# RCMx1_Rev_02.net
KiCad netlist of a schematic drawn in EAGLE
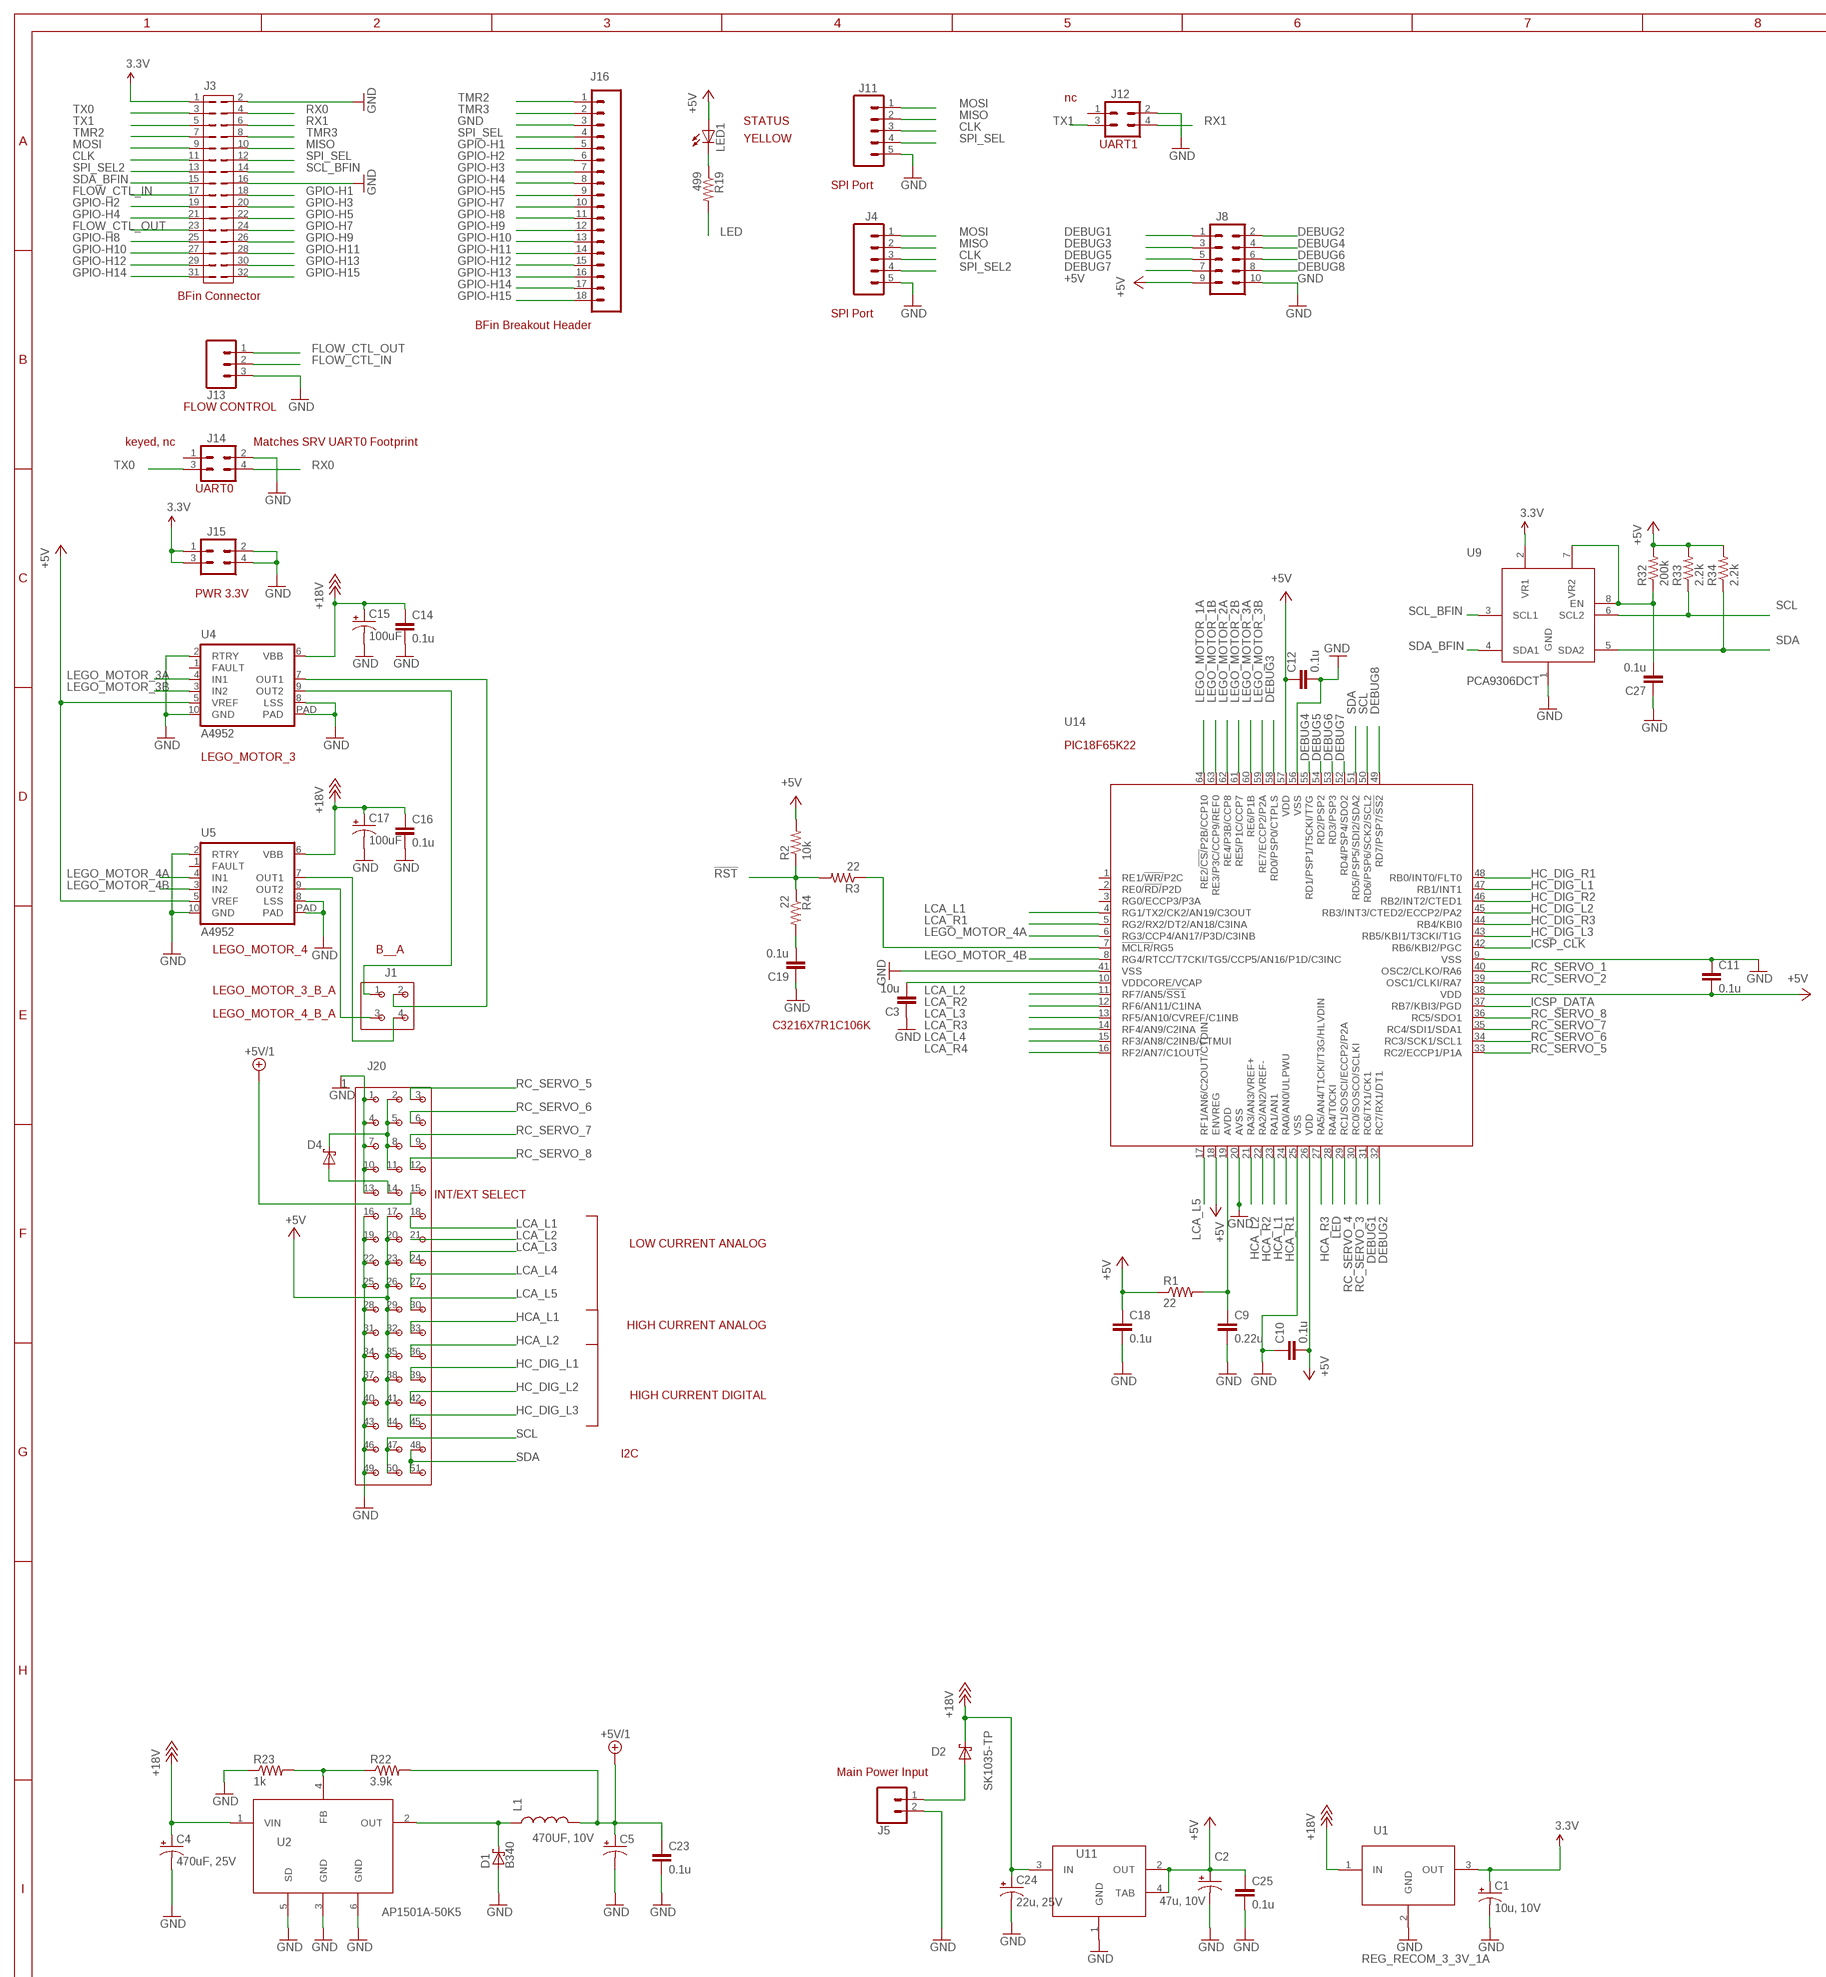
[diagram p0: schematic, sheet 1, part 1 of 2]
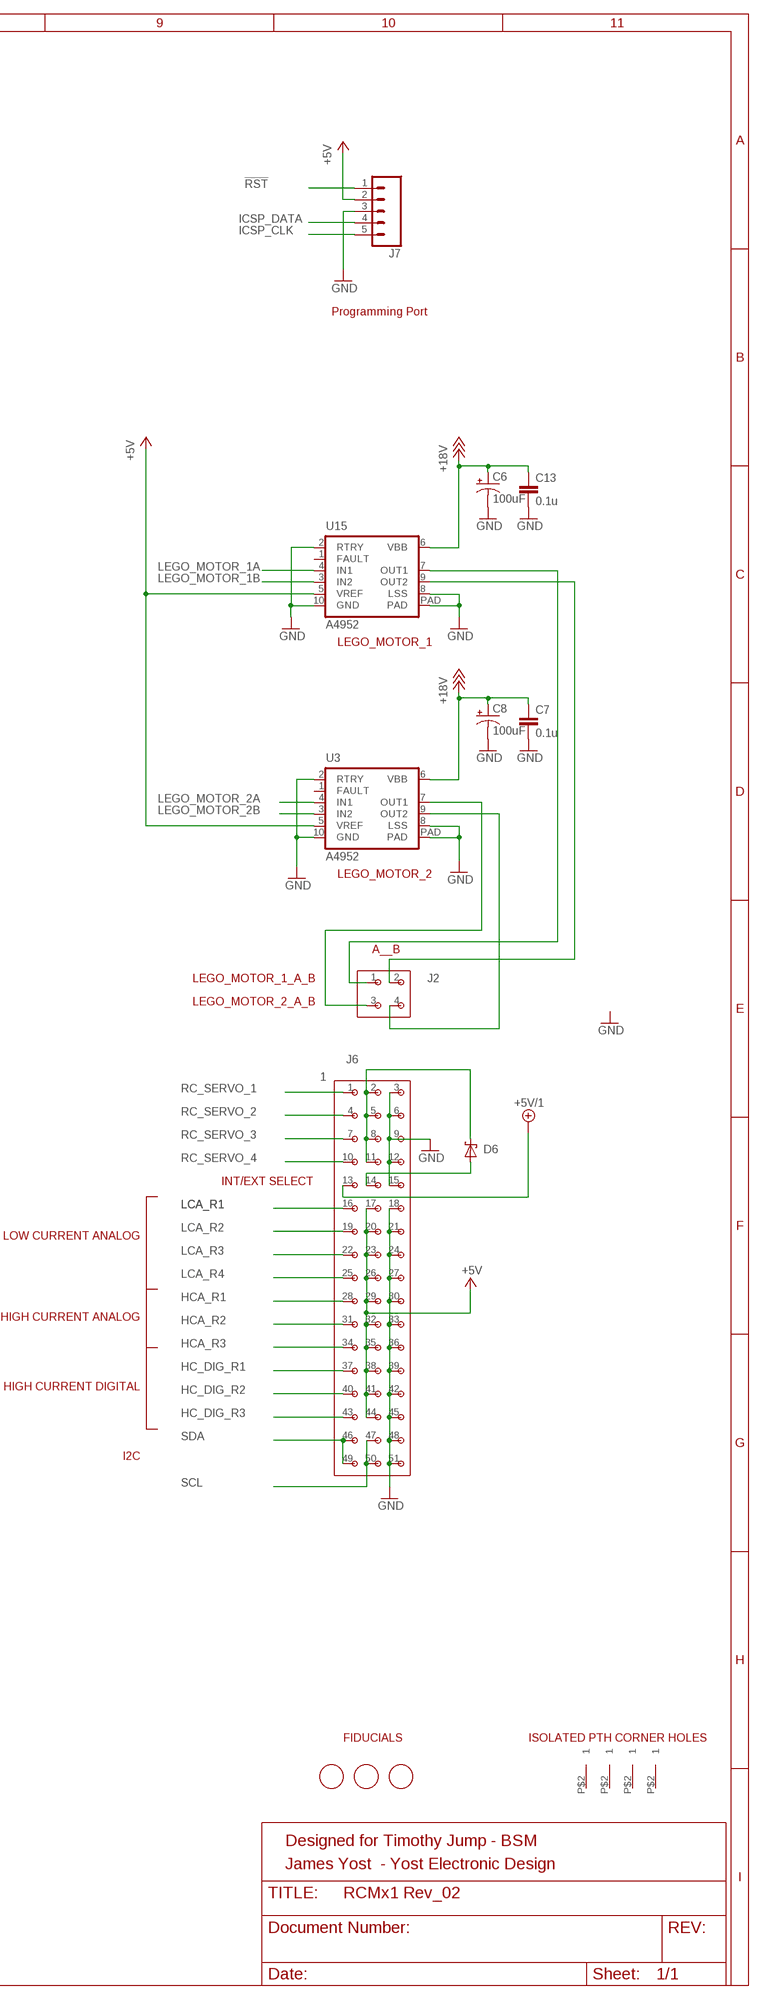
[diagram p1: schematic, sheet 1, part 2 of 2]

(export (version "E")
  (design (tool "Eeschema 10.0.6"))
  (components
    (comp (ref "C1")
      (value "10u, 10V")
      (footprint "eagle-import:EIA3216")
      (libsource (lib "eagle-import") (part "CAP_POL1206"))
    )
    (comp (ref "C2")
      (value "47u, 10V")
      (footprint "eagle-import:CAP1210_POL")
      (libsource (lib "eagle-import") (part "CAP_1210_POL"))
    )
    (comp (ref "C3")
      (value "10u")
      (footprint "eagle-import:1206")
      (libsource (lib "eagle-import") (part "CAP1206"))
    )
    (comp (ref "C4")
      (value "470uF, 25V")
      (footprint "eagle-import:PANASONIC_G")
      (libsource (lib "eagle-import") (part "CAP_POLG"))
    )
    (comp (ref "C5")
      (value "470UF, 10V")
      (footprint "eagle-import:PANASONIC_F")
      (libsource (lib "eagle-import") (part "CAP_ELT_PANASONIC_470UF"))
    )
    (comp (ref "C6")
      (value "100uF")
      (footprint "eagle-import:PANASONIC_D")
      (libsource (lib "eagle-import") (part "CAP_POLD"))
    )
    (comp (ref "C7")
      (value "0.1u")
      (footprint "eagle-import:0805")
      (libsource (lib "eagle-import") (part "CAP0805"))
    )
    (comp (ref "C8")
      (value "100uF")
      (footprint "eagle-import:PANASONIC_D")
      (libsource (lib "eagle-import") (part "CAP_POLD"))
    )
    (comp (ref "C9")
      (value "0.22u")
      (footprint "eagle-import:0805")
      (libsource (lib "eagle-import") (part "CAP0805"))
    )
    (comp (ref "C10")
      (value "0.1u")
      (footprint "eagle-import:0805")
      (libsource (lib "eagle-import") (part "CAP0805"))
    )
    (comp (ref "C11")
      (value "0.1u")
      (footprint "eagle-import:0805")
      (libsource (lib "eagle-import") (part "CAP0805"))
    )
    (comp (ref "C12")
      (value "0.1u")
      (footprint "eagle-import:0805")
      (libsource (lib "eagle-import") (part "CAP0805"))
    )
    (comp (ref "C13")
      (value "0.1u")
      (footprint "eagle-import:0805")
      (libsource (lib "eagle-import") (part "CAP0805"))
    )
    (comp (ref "C14")
      (value "0.1u")
      (footprint "eagle-import:0805")
      (libsource (lib "eagle-import") (part "CAP0805"))
    )
    (comp (ref "C15")
      (value "100uF")
      (footprint "eagle-import:PANASONIC_D")
      (libsource (lib "eagle-import") (part "CAP_POLD"))
    )
    (comp (ref "C16")
      (value "0.1u")
      (footprint "eagle-import:0805")
      (libsource (lib "eagle-import") (part "CAP0805"))
    )
    (comp (ref "C17")
      (value "100uF")
      (footprint "eagle-import:PANASONIC_D")
      (libsource (lib "eagle-import") (part "CAP_POLD"))
    )
    (comp (ref "C18")
      (value "0.1u")
      (footprint "eagle-import:0805")
      (libsource (lib "eagle-import") (part "CAP0805"))
    )
    (comp (ref "C19")
      (value "0.1u")
      (footprint "eagle-import:0805")
      (libsource (lib "eagle-import") (part "CAP0805"))
    )
    (comp (ref "C23")
      (value "0.1u")
      (footprint "eagle-import:0805")
      (libsource (lib "eagle-import") (part "CAP0805"))
    )
    (comp (ref "C24")
      (value "22u, 25V")
      (footprint "eagle-import:CAP1210_POL")
      (libsource (lib "eagle-import") (part "CAP_1210_POL"))
    )
    (comp (ref "C25")
      (value "0.1u")
      (footprint "eagle-import:0805")
      (libsource (lib "eagle-import") (part "CAP0805"))
    )
    (comp (ref "C27")
      (value "0.1u")
      (footprint "eagle-import:0805")
      (libsource (lib "eagle-import") (part "CAP0805"))
    )
    (comp (ref "D1")
      (value "B340")
      (footprint "eagle-import:SMA_DO214AC")
      (libsource (lib "eagle-import") (part "B340"))
    )
    (comp (ref "D2")
      (value "SK1035-TP")
      (footprint "eagle-import:DO214AB")
      (libsource (lib "eagle-import") (part "SK1035-TP"))
    )
    (comp (ref "D4")
      (value "SK1035-TP")
      (footprint "eagle-import:DO214AB")
      (libsource (lib "eagle-import") (part "SK1035-TP"))
    )
    (comp (ref "D6")
      (value "SK1035-TP")
      (footprint "eagle-import:DO214AB")
      (libsource (lib "eagle-import") (part "SK1035-TP"))
    )
    (comp (ref "FID1")
      (value "FIDUCIAL")
      (footprint "eagle-import:FIDUCIAL_1MM")
      (libsource (lib "eagle-import") (part "FIDUCIAL"))
    )
    (comp (ref "FID2")
      (value "FIDUCIAL")
      (footprint "eagle-import:FIDUCIAL_1MM")
      (libsource (lib "eagle-import") (part "FIDUCIAL"))
    )
    (comp (ref "FID3")
      (value "FIDUCIAL")
      (footprint "eagle-import:FIDUCIAL_1MM")
      (libsource (lib "eagle-import") (part "FIDUCIAL"))
    )
    (comp (ref "J1")
      (value "CON_2X2_0_100")
      (footprint "eagle-import:CON_2X2_0_100")
      (libsource (lib "eagle-import") (part "CON_2X2_0_100"))
    )
    (comp (ref "J2")
      (value "CON_2X2_0_100")
      (footprint "eagle-import:CON_2X2_0_100")
      (libsource (lib "eagle-import") (part "CON_2X2_0_100"))
    )
    (comp (ref "J3")
      (value "CON_2X16_0_100")
      (footprint "eagle-import:CON_2X16_0_100")
      (libsource (lib "eagle-import") (part "CON_2X16_0_100"))
    )
    (comp (ref "J4")
      (value "M05PTH")
      (footprint "eagle-import:1X05")
      (libsource (lib "eagle-import") (part "M05PTH"))
    )
    (comp (ref "J5")
      (value "M02NG")
      (footprint "eagle-import:1X02")
      (libsource (lib "eagle-import") (part "M02NG"))
    )
    (comp (ref "J6")
      (value "CON_3X17_0_100")
      (footprint "eagle-import:CON_3X17_0_100")
      (libsource (lib "eagle-import") (part "CON_3X17_0_100"))
    )
    (comp (ref "J7")
      (value "M05PTH")
      (footprint "eagle-import:1X05")
      (libsource (lib "eagle-import") (part "SparkFun-Connectors_M05PTH"))
    )
    (comp (ref "J8")
      (value "M05X2PTH")
      (footprint "eagle-import:AVR_ICSP")
      (libsource (lib "eagle-import") (part "M05X2PTH"))
    )
    (comp (ref "J11")
      (value "M05PTH")
      (footprint "eagle-import:1X05")
      (libsource (lib "eagle-import") (part "M05PTH"))
    )
    (comp (ref "J12")
      (value "CON2X2")
      (footprint "eagle-import:CON2X2")
      (libsource (lib "eagle-import") (part "CON2X2"))
    )
    (comp (ref "J13")
      (value "M03PTH")
      (footprint "eagle-import:1X03")
      (libsource (lib "eagle-import") (part "M03PTH"))
    )
    (comp (ref "J14")
      (value "CON2X2")
      (footprint "eagle-import:CON2X2")
      (libsource (lib "eagle-import") (part "CON2X2"))
    )
    (comp (ref "J15")
      (value "CON2X2")
      (footprint "eagle-import:CON2X2")
      (libsource (lib "eagle-import") (part "CON2X2"))
    )
    (comp (ref "J16")
      (value "CON1X18")
      (footprint "eagle-import:CON1X18")
      (libsource (lib "eagle-import") (part "CON1X18"))
    )
    (comp (ref "J20")
      (value "CON_3X17_0_100")
      (footprint "eagle-import:CON_3X17_0_100")
      (libsource (lib "eagle-import") (part "CON_3X17_0_100"))
    )
    (comp (ref "L1")
      (value "IND_47UH_COILTRONICS_2_95A")
      (footprint "eagle-import:IND_PADS_SMT")
      (libsource (lib "eagle-import") (part "IND_47UH_COILTRONICS_2_95A"))
    )
    (comp (ref "LED1")
      (value "LEDCHIP-LED0805")
      (footprint "eagle-import:CHIP-LED0805")
      (libsource (lib "eagle-import") (part "LEDCHIP-LED0805"))
    )
    (comp (ref "R1")
      (value "22")
      (footprint "eagle-import:0805")
      (libsource (lib "eagle-import") (part "RESISTOR"))
    )
    (comp (ref "R2")
      (value "10k")
      (footprint "eagle-import:0805")
      (libsource (lib "eagle-import") (part "RESISTOR"))
    )
    (comp (ref "R3")
      (value "22")
      (footprint "eagle-import:0805")
      (libsource (lib "eagle-import") (part "RESISTOR"))
    )
    (comp (ref "R4")
      (value "22")
      (footprint "eagle-import:0805")
      (libsource (lib "eagle-import") (part "RESISTOR"))
    )
    (comp (ref "R19")
      (value "499")
      (footprint "eagle-import:0805")
      (libsource (lib "eagle-import") (part "RESISTOR"))
    )
    (comp (ref "R22")
      (value "3.9k")
      (footprint "eagle-import:0805")
      (libsource (lib "eagle-import") (part "RESISTOR"))
    )
    (comp (ref "R23")
      (value "1k")
      (footprint "eagle-import:0805")
      (libsource (lib "eagle-import") (part "RESISTOR"))
    )
    (comp (ref "R32")
      (value "200k")
      (footprint "eagle-import:0805")
      (libsource (lib "eagle-import") (part "RESISTOR"))
    )
    (comp (ref "R33")
      (value "2.2k")
      (footprint "eagle-import:0805")
      (libsource (lib "eagle-import") (part "RESISTOR"))
    )
    (comp (ref "R34")
      (value "2.2k")
      (footprint "eagle-import:0805")
      (libsource (lib "eagle-import") (part "RESISTOR"))
    )
    (comp (ref "U$1")
      (value "GNDPAD")
      (footprint "eagle-import:GNDPAD")
      (libsource (lib "eagle-import") (part "GNDPAD"))
    )
    (comp (ref "U$2")
      (value "GNDPAD")
      (footprint "eagle-import:GNDPAD")
      (libsource (lib "eagle-import") (part "GNDPAD"))
    )
    (comp (ref "U$7")
      (value "GNDPAD")
      (footprint "eagle-import:GNDPAD")
      (libsource (lib "eagle-import") (part "GNDPAD"))
    )
    (comp (ref "U$8")
      (value "GNDPAD")
      (footprint "eagle-import:GNDPAD")
      (libsource (lib "eagle-import") (part "GNDPAD"))
    )
    (comp (ref "U1")
      (value "REG_RECOM_3_3V_1A")
      (footprint "eagle-import:REG_RECOM_3_3V_1A")
      (libsource (lib "eagle-import") (part "REG_RECOM_3_3V_1A"))
    )
    (comp (ref "U2")
      (value "AP1501A-50K5")
      (footprint "eagle-import:TO263-5")
      (libsource (lib "eagle-import") (part "AP1501A-50K5"))
    )
    (comp (ref "U3")
      (value "A4952")
      (footprint "eagle-import:MSOP10_W_THERMAL_PAD")
      (libsource (lib "eagle-import") (part "A4952"))
    )
    (comp (ref "U4")
      (value "A4952")
      (footprint "eagle-import:MSOP10_W_THERMAL_PAD")
      (libsource (lib "eagle-import") (part "A4952"))
    )
    (comp (ref "U5")
      (value "A4952")
      (footprint "eagle-import:MSOP10_W_THERMAL_PAD")
      (libsource (lib "eagle-import") (part "A4952"))
    )
    (comp (ref "U9")
      (value "PCA9306DCT")
      (footprint "eagle-import:TEST08")
      (libsource (lib "eagle-import") (part "PCA9306DCT"))
    )
    (comp (ref "U11")
      (value "TLV1117-5")
      (footprint "eagle-import:SOT223")
      (libsource (lib "eagle-import") (part "TLV1117-5"))
    )
    (comp (ref "U14")
      (value "MICRO_C_PIC18F65K22")
      (footprint "eagle-import:64PIN_TQFP_10X10X1MM")
      (libsource (lib "eagle-import") (part "MICRO_C_PIC18F65K22"))
    )
    (comp (ref "U15")
      (value "A4952")
      (footprint "eagle-import:MSOP10_W_THERMAL_PAD")
      (libsource (lib "eagle-import") (part "A4952"))
    )
  )
  (nets
    (net (code "1") (name "+5V") (class "Default")
      (node (ref "C10") (pin "2") (pinfunction "2_2") (pintype "passive"))
      (node (ref "C11") (pin "2") (pinfunction "2_2") (pintype "passive"))
      (node (ref "C12") (pin "1") (pinfunction "1_1") (pintype "passive"))
      (node (ref "C18") (pin "1") (pinfunction "1_1") (pintype "passive"))
      (node (ref "C2") (pin "1") (pinfunction "+_1") (pintype "passive"))
      (node (ref "C25") (pin "1") (pinfunction "1_1") (pintype "passive"))
      (node (ref "J20") (pin "17") (pinfunction "17_17") (pintype "passive"))
      (node (ref "J20") (pin "20") (pinfunction "20_20") (pintype "passive"))
      (node (ref "J20") (pin "23") (pinfunction "23_23") (pintype "passive"))
      (node (ref "J20") (pin "26") (pinfunction "26_26") (pintype "passive"))
      (node (ref "J20") (pin "29") (pinfunction "29_29") (pintype "passive"))
      (node (ref "J20") (pin "32") (pinfunction "32_32") (pintype "passive"))
      (node (ref "J20") (pin "35") (pinfunction "35_35") (pintype "passive"))
      (node (ref "J20") (pin "38") (pinfunction "38_38") (pintype "passive"))
      (node (ref "J20") (pin "41") (pinfunction "41_41") (pintype "passive"))
      (node (ref "J20") (pin "44") (pinfunction "44_44") (pintype "passive"))
      (node (ref "J6") (pin "17") (pinfunction "17_17") (pintype "passive"))
      (node (ref "J6") (pin "20") (pinfunction "20_20") (pintype "passive"))
      (node (ref "J6") (pin "23") (pinfunction "23_23") (pintype "passive"))
      (node (ref "J6") (pin "26") (pinfunction "26_26") (pintype "passive"))
      (node (ref "J6") (pin "29") (pinfunction "29_29") (pintype "passive"))
      (node (ref "J6") (pin "32") (pinfunction "32_32") (pintype "passive"))
      (node (ref "J6") (pin "35") (pinfunction "35_35") (pintype "passive"))
      (node (ref "J6") (pin "38") (pinfunction "38_38") (pintype "passive"))
      (node (ref "J6") (pin "41") (pinfunction "41_41") (pintype "passive"))
      (node (ref "J6") (pin "44") (pinfunction "44_44") (pintype "passive"))
      (node (ref "J7") (pin "2") (pinfunction "2_2") (pintype "passive"))
      (node (ref "J8") (pin "9") (pinfunction "9_9") (pintype "passive"))
      (node (ref "LED1") (pin "A") (pinfunction "A_A") (pintype "passive"))
      (node (ref "R1") (pin "1") (pinfunction "1_1") (pintype "passive"))
      (node (ref "R2") (pin "2") (pinfunction "2_2") (pintype "passive"))
      (node (ref "R32") (pin "2") (pinfunction "2_2") (pintype "passive"))
      (node (ref "R33") (pin "2") (pinfunction "2_2") (pintype "passive"))
      (node (ref "R34") (pin "2") (pinfunction "2_2") (pintype "passive"))
      (node (ref "U11") (pin "2") (pinfunction "OUT_2") (pintype "bidirectional"))
      (node (ref "U11") (pin "4") (pinfunction "TAB_4") (pintype "bidirectional"))
      (node (ref "U14") (pin "18") (pinfunction "ENVREG_18") (pintype "input"))
      (node (ref "U14") (pin "26") (pinfunction "VDD_26") (pintype "power_in"))
      (node (ref "U14") (pin "38") (pinfunction "VDD_38") (pintype "power_in"))
      (node (ref "U14") (pin "57") (pinfunction "VDD_57") (pintype "power_in"))
      (node (ref "U15") (pin "5") (pinfunction "VREF_5") (pintype "passive"))
      (node (ref "U3") (pin "5") (pinfunction "VREF_5") (pintype "passive"))
      (node (ref "U4") (pin "5") (pinfunction "VREF_5") (pintype "passive"))
      (node (ref "U5") (pin "5") (pinfunction "VREF_5") (pintype "passive"))
    )
    (net (code "2") (name "+5V{slash}1") (class "Default")
      (node (ref "C23") (pin "1") (pinfunction "1_1") (pintype "passive"))
      (node (ref "C5") (pin "+") (pinfunction "+_+") (pintype "passive"))
      (node (ref "J20") (pin "15") (pinfunction "15_15") (pintype "passive"))
      (node (ref "J6") (pin "13") (pinfunction "13_13") (pintype "passive"))
      (node (ref "L1") (pin "2") (pinfunction "2_2") (pintype "passive"))
      (node (ref "R22") (pin "2") (pinfunction "2_2") (pintype "passive"))
    )
    (net (code "3") (name "+18V") (class "Default")
      (node (ref "C13") (pin "1") (pinfunction "1_1") (pintype "passive"))
      (node (ref "C14") (pin "1") (pinfunction "1_1") (pintype "passive"))
      (node (ref "C15") (pin "+") (pinfunction "+_+") (pintype "passive"))
      (node (ref "C16") (pin "1") (pinfunction "1_1") (pintype "passive"))
      (node (ref "C17") (pin "+") (pinfunction "+_+") (pintype "passive"))
      (node (ref "C24") (pin "1") (pinfunction "+_1") (pintype "passive"))
      (node (ref "C4") (pin "+") (pinfunction "+_+") (pintype "passive"))
      (node (ref "C6") (pin "+") (pinfunction "+_+") (pintype "passive"))
      (node (ref "C7") (pin "1") (pinfunction "1_1") (pintype "passive"))
      (node (ref "C8") (pin "+") (pinfunction "+_+") (pintype "passive"))
      (node (ref "D2") (pin "1") (pinfunction "C_1") (pintype "passive"))
      (node (ref "U1") (pin "1") (pinfunction "IN_1") (pintype "bidirectional"))
      (node (ref "U11") (pin "3") (pinfunction "IN_3") (pintype "bidirectional"))
      (node (ref "U15") (pin "6") (pinfunction "VBB_6") (pintype "input"))
      (node (ref "U2") (pin "1") (pinfunction "VIN_1") (pintype "bidirectional"))
      (node (ref "U3") (pin "6") (pinfunction "VBB_6") (pintype "input"))
      (node (ref "U4") (pin "6") (pinfunction "VBB_6") (pintype "input"))
      (node (ref "U5") (pin "6") (pinfunction "VBB_6") (pintype "input"))
    )
    (net (code "4") (name "/CLK") (class "Default")
      (node (ref "J11") (pin "3") (pinfunction "3_3") (pintype "passive"))
      (node (ref "J3") (pin "11") (pinfunction "11_11") (pintype "passive"))
      (node (ref "J4") (pin "3") (pinfunction "3_3") (pintype "passive"))
    )
    (net (code "5") (name "/DEBUG1") (class "Default")
      (node (ref "J8") (pin "1") (pinfunction "1_1") (pintype "passive"))
      (node (ref "U14") (pin "31") (pinfunction "RC6/TX1/CK1_31") (pintype "bidirectional"))
    )
    (net (code "6") (name "/DEBUG2") (class "Default")
      (node (ref "J8") (pin "2") (pinfunction "2_2") (pintype "passive"))
      (node (ref "U14") (pin "32") (pinfunction "RC7/RX1/DT1_32") (pintype "bidirectional"))
    )
    (net (code "7") (name "/DEBUG3") (class "Default")
      (node (ref "J8") (pin "3") (pinfunction "3_3") (pintype "passive"))
      (node (ref "U14") (pin "58") (pinfunction "RD0/PSP0/CTPLS_58") (pintype "bidirectional"))
    )
    (net (code "8") (name "/DEBUG4") (class "Default")
      (node (ref "J8") (pin "4") (pinfunction "4_4") (pintype "passive"))
      (node (ref "U14") (pin "55") (pinfunction "RD1/PSP1/T5CKI/T7G_55") (pintype "bidirectional"))
    )
    (net (code "9") (name "/DEBUG5") (class "Default")
      (node (ref "J8") (pin "5") (pinfunction "5_5") (pintype "passive"))
      (node (ref "U14") (pin "54") (pinfunction "RD2/PSP2_54") (pintype "bidirectional"))
    )
    (net (code "10") (name "/DEBUG6") (class "Default")
      (node (ref "J8") (pin "6") (pinfunction "6_6") (pintype "passive"))
      (node (ref "U14") (pin "53") (pinfunction "RD3/PSP3_53") (pintype "bidirectional"))
    )
    (net (code "11") (name "/DEBUG7") (class "Default")
      (node (ref "J8") (pin "7") (pinfunction "7_7") (pintype "passive"))
      (node (ref "U14") (pin "52") (pinfunction "RD4/PSP4/SDO2_52") (pintype "bidirectional"))
    )
    (net (code "12") (name "/DEBUG8") (class "Default")
      (node (ref "J8") (pin "8") (pinfunction "8_8") (pintype "passive"))
      (node (ref "U14") (pin "49") (pinfunction "RD7/PSP7/~{SS2}_49") (pintype "bidirectional"))
    )
    (net (code "13") (name "/FLOW_CTL_IN") (class "Default")
      (node (ref "J13") (pin "2") (pinfunction "2_2") (pintype "passive"))
      (node (ref "J3") (pin "17") (pinfunction "17_17") (pintype "passive"))
    )
    (net (code "14") (name "/FLOW_CTL_OUT") (class "Default")
      (node (ref "J13") (pin "1") (pinfunction "1_1") (pintype "passive"))
      (node (ref "J3") (pin "23") (pinfunction "23_23") (pintype "passive"))
    )
    (net (code "15") (name "/GPIO-H1") (class "Default")
      (node (ref "J16") (pin "5") (pinfunction "5_5") (pintype "passive"))
      (node (ref "J3") (pin "18") (pinfunction "18_18") (pintype "passive"))
    )
    (net (code "16") (name "/GPIO-H2") (class "Default")
      (node (ref "J16") (pin "6") (pinfunction "6_6") (pintype "passive"))
      (node (ref "J3") (pin "19") (pinfunction "19_19") (pintype "passive"))
    )
    (net (code "17") (name "/GPIO-H3") (class "Default")
      (node (ref "J16") (pin "7") (pinfunction "7_7") (pintype "passive"))
      (node (ref "J3") (pin "20") (pinfunction "20_20") (pintype "passive"))
    )
    (net (code "18") (name "/GPIO-H4") (class "Default")
      (node (ref "J16") (pin "8") (pinfunction "8_8") (pintype "passive"))
      (node (ref "J3") (pin "21") (pinfunction "21_21") (pintype "passive"))
    )
    (net (code "19") (name "/GPIO-H5") (class "Default")
      (node (ref "J16") (pin "9") (pinfunction "9_9") (pintype "passive"))
      (node (ref "J3") (pin "22") (pinfunction "22_22") (pintype "passive"))
    )
    (net (code "20") (name "/GPIO-H7") (class "Default")
      (node (ref "J16") (pin "10") (pinfunction "10_10") (pintype "passive"))
      (node (ref "J3") (pin "24") (pinfunction "24_24") (pintype "passive"))
    )
    (net (code "21") (name "/GPIO-H8") (class "Default")
      (node (ref "J16") (pin "11") (pinfunction "11_11") (pintype "passive"))
      (node (ref "J3") (pin "25") (pinfunction "25_25") (pintype "passive"))
    )
    (net (code "22") (name "/GPIO-H9") (class "Default")
      (node (ref "J16") (pin "12") (pinfunction "12_12") (pintype "passive"))
      (node (ref "J3") (pin "26") (pinfunction "26_26") (pintype "passive"))
    )
    (net (code "23") (name "/GPIO-H10") (class "Default")
      (node (ref "J16") (pin "13") (pinfunction "13_13") (pintype "passive"))
      (node (ref "J3") (pin "27") (pinfunction "27_27") (pintype "passive"))
    )
    (net (code "24") (name "/GPIO-H11") (class "Default")
      (node (ref "J16") (pin "14") (pinfunction "14_14") (pintype "passive"))
      (node (ref "J3") (pin "28") (pinfunction "28_28") (pintype "passive"))
    )
    (net (code "25") (name "/GPIO-H12") (class "Default")
      (node (ref "J16") (pin "15") (pinfunction "15_15") (pintype "passive"))
      (node (ref "J3") (pin "29") (pinfunction "29_29") (pintype "passive"))
    )
    (net (code "26") (name "/GPIO-H13") (class "Default")
      (node (ref "J16") (pin "16") (pinfunction "16_16") (pintype "passive"))
      (node (ref "J3") (pin "30") (pinfunction "30_30") (pintype "passive"))
    )
    (net (code "27") (name "/GPIO-H14") (class "Default")
      (node (ref "J16") (pin "17") (pinfunction "17_17") (pintype "passive"))
      (node (ref "J3") (pin "31") (pinfunction "31_31") (pintype "passive"))
    )
    (net (code "28") (name "/GPIO-H15") (class "Default")
      (node (ref "J16") (pin "18") (pinfunction "18_18") (pintype "passive"))
      (node (ref "J3") (pin "32") (pinfunction "32_32") (pintype "passive"))
    )
    (net (code "29") (name "/HCA_L1") (class "Default")
      (node (ref "J20") (pin "33") (pinfunction "33_33") (pintype "passive"))
      (node (ref "U14") (pin "23") (pinfunction "RA1/AN1_23") (pintype "bidirectional"))
    )
    (net (code "30") (name "/HCA_L2") (class "Default")
      (node (ref "J20") (pin "36") (pinfunction "36_36") (pintype "passive"))
      (node (ref "U14") (pin "21") (pinfunction "RA3/AN3/VREF+_21") (pintype "bidirectional"))
    )
    (net (code "31") (name "/HCA_R1") (class "Default")
      (node (ref "J6") (pin "28") (pinfunction "28_28") (pintype "passive"))
      (node (ref "U14") (pin "24") (pinfunction "RA0/AN0/ULPWU_24") (pintype "bidirectional"))
    )
    (net (code "32") (name "/HCA_R2") (class "Default")
      (node (ref "J6") (pin "31") (pinfunction "31_31") (pintype "passive"))
      (node (ref "U14") (pin "22") (pinfunction "RA2/AN2/VREF-_22") (pintype "bidirectional"))
    )
    (net (code "33") (name "/HCA_R3") (class "Default")
      (node (ref "J6") (pin "34") (pinfunction "34_34") (pintype "passive"))
      (node (ref "U14") (pin "27") (pinfunction "RA5/AN4/T1CKI/T3G/HLVDIN_27") (pintype "bidirectional"))
    )
    (net (code "34") (name "/HC_DIG_L1") (class "Default")
      (node (ref "J20") (pin "39") (pinfunction "39_39") (pintype "passive"))
      (node (ref "U14") (pin "47") (pinfunction "RB1/INT1_47") (pintype "bidirectional"))
    )
    (net (code "35") (name "/HC_DIG_L2") (class "Default")
      (node (ref "J20") (pin "42") (pinfunction "42_42") (pintype "passive"))
      (node (ref "U14") (pin "45") (pinfunction "RB3/INT3/CTED2/ECCP2/PA2_45") (pintype "bidirectional"))
    )
    (net (code "36") (name "/HC_DIG_L3") (class "Default")
      (node (ref "J20") (pin "45") (pinfunction "45_45") (pintype "passive"))
      (node (ref "U14") (pin "43") (pinfunction "RB5/KBI1/T3CKI/T1G_43") (pintype "bidirectional"))
    )
    (net (code "37") (name "/HC_DIG_R1") (class "Default")
      (node (ref "J6") (pin "37") (pinfunction "37_37") (pintype "passive"))
      (node (ref "U14") (pin "48") (pinfunction "RB0/INT0/FLT0_48") (pintype "bidirectional"))
    )
    (net (code "38") (name "/HC_DIG_R2") (class "Default")
      (node (ref "J6") (pin "40") (pinfunction "40_40") (pintype "passive"))
      (node (ref "U14") (pin "46") (pinfunction "RB2/INT2/CTED1_46") (pintype "bidirectional"))
    )
    (net (code "39") (name "/HC_DIG_R3") (class "Default")
      (node (ref "J6") (pin "43") (pinfunction "43_43") (pintype "passive"))
      (node (ref "U14") (pin "44") (pinfunction "RB4/KBI0_44") (pintype "bidirectional"))
    )
    (net (code "40") (name "/ICSP_CLK") (class "Default")
      (node (ref "J7") (pin "5") (pinfunction "5_5") (pintype "passive"))
      (node (ref "U14") (pin "42") (pinfunction "RB6/KBI2/PGC_42") (pintype "bidirectional"))
    )
    (net (code "41") (name "/ICSP_DATA") (class "Default")
      (node (ref "J7") (pin "4") (pinfunction "4_4") (pintype "passive"))
      (node (ref "U14") (pin "37") (pinfunction "RB7/KBI3/PGD_37") (pintype "bidirectional"))
    )
    (net (code "42") (name "/LCA_L1") (class "Default")
      (node (ref "J20") (pin "18") (pinfunction "18_18") (pintype "passive"))
      (node (ref "U14") (pin "4") (pinfunction "RG1/TX2/CK2/AN19/C3OUT_4") (pintype "bidirectional"))
    )
    (net (code "43") (name "/LCA_L2") (class "Default")
      (node (ref "J20") (pin "21") (pinfunction "21_21") (pintype "passive"))
      (node (ref "U14") (pin "11") (pinfunction "RF7/AN5/~{SS1}_11") (pintype "bidirectional"))
    )
    (net (code "44") (name "/LCA_L3") (class "Default")
      (node (ref "J20") (pin "24") (pinfunction "24_24") (pintype "passive"))
      (node (ref "U14") (pin "13") (pinfunction "RF5/AN10/CVREF/C1INB_13") (pintype "bidirectional"))
    )
    (net (code "45") (name "/LCA_L4") (class "Default")
      (node (ref "J20") (pin "27") (pinfunction "27_27") (pintype "passive"))
      (node (ref "U14") (pin "15") (pinfunction "RF3/AN8/C2INB/CTMUI_15") (pintype "bidirectional"))
    )
    (net (code "46") (name "/LCA_L5") (class "Default")
      (node (ref "J20") (pin "30") (pinfunction "30_30") (pintype "passive"))
      (node (ref "U14") (pin "17") (pinfunction "RF1/AN6/C2OUT/CTDIN_17") (pintype "bidirectional"))
    )
    (net (code "47") (name "/LCA_R1") (class "Default")
      (node (ref "J6") (pin "16") (pinfunction "16_16") (pintype "passive"))
      (node (ref "U14") (pin "5") (pinfunction "RG2/RX2/DT2/AN18/C3INA_5") (pintype "bidirectional"))
    )
    (net (code "48") (name "/LCA_R2") (class "Default")
      (node (ref "J6") (pin "19") (pinfunction "19_19") (pintype "passive"))
      (node (ref "U14") (pin "12") (pinfunction "RF6/AN11/C1INA_12") (pintype "bidirectional"))
    )
    (net (code "49") (name "/LCA_R3") (class "Default")
      (node (ref "J6") (pin "22") (pinfunction "22_22") (pintype "passive"))
      (node (ref "U14") (pin "14") (pinfunction "RF4/AN9/C2INA_14") (pintype "bidirectional"))
    )
    (net (code "50") (name "/LCA_R4") (class "Default")
      (node (ref "J6") (pin "25") (pinfunction "25_25") (pintype "passive"))
      (node (ref "U14") (pin "16") (pinfunction "RF2/AN7/C1OUT_16") (pintype "bidirectional"))
    )
    (net (code "51") (name "/LED") (class "Default")
      (node (ref "R19") (pin "2") (pinfunction "2_2") (pintype "passive"))
      (node (ref "U14") (pin "28") (pinfunction "RA4/T0CKI_28") (pintype "bidirectional"))
    )
    (net (code "52") (name "/LEGO_MOTOR_1A") (class "Default")
      (node (ref "U14") (pin "64") (pinfunction "RE2/~{CS/}P2B/CCP10_64") (pintype "bidirectional"))
      (node (ref "U15") (pin "4") (pinfunction "IN1_4") (pintype "input"))
    )
    (net (code "53") (name "/LEGO_MOTOR_1B") (class "Default")
      (node (ref "U14") (pin "63") (pinfunction "RE3/P3C/CCP9/REF0_63") (pintype "bidirectional"))
      (node (ref "U15") (pin "3") (pinfunction "IN2_3") (pintype "input"))
    )
    (net (code "54") (name "/LEGO_MOTOR_2A") (class "Default")
      (node (ref "U14") (pin "62") (pinfunction "RE4/P3B/CCP8_62") (pintype "bidirectional"))
      (node (ref "U3") (pin "4") (pinfunction "IN1_4") (pintype "input"))
    )
    (net (code "55") (name "/LEGO_MOTOR_2B") (class "Default")
      (node (ref "U14") (pin "61") (pinfunction "RE5/P1C/CCP7_61") (pintype "bidirectional"))
      (node (ref "U3") (pin "3") (pinfunction "IN2_3") (pintype "input"))
    )
    (net (code "56") (name "/LEGO_MOTOR_3A") (class "Default")
      (node (ref "U14") (pin "60") (pinfunction "RE6/P1B_60") (pintype "bidirectional"))
      (node (ref "U4") (pin "4") (pinfunction "IN1_4") (pintype "input"))
    )
    (net (code "57") (name "/LEGO_MOTOR_3B") (class "Default")
      (node (ref "U14") (pin "59") (pinfunction "RE7/ECCP2/P2A_59") (pintype "bidirectional"))
      (node (ref "U4") (pin "3") (pinfunction "IN2_3") (pintype "input"))
    )
    (net (code "58") (name "/LEGO_MOTOR_4A") (class "Default")
      (node (ref "U14") (pin "6") (pinfunction "RG3/CCP4/AN17/P3D/C3INB_6") (pintype "bidirectional"))
      (node (ref "U5") (pin "4") (pinfunction "IN1_4") (pintype "input"))
    )
    (net (code "59") (name "/LEGO_MOTOR_4B") (class "Default")
      (node (ref "U14") (pin "8") (pinfunction "RG4/RTCC/T7CKI/TG5/CCP5/AN16/P1D/C3INC_8") (pintype "bidirectional"))
      (node (ref "U5") (pin "3") (pinfunction "IN2_3") (pintype "input"))
    )
    (net (code "60") (name "/MISO") (class "Default")
      (node (ref "J11") (pin "2") (pinfunction "2_2") (pintype "passive"))
      (node (ref "J3") (pin "10") (pinfunction "10_10") (pintype "passive"))
      (node (ref "J4") (pin "2") (pinfunction "2_2") (pintype "passive"))
    )
    (net (code "61") (name "/MOSI") (class "Default")
      (node (ref "J11") (pin "1") (pinfunction "1_1") (pintype "passive"))
      (node (ref "J3") (pin "9") (pinfunction "9_9") (pintype "passive"))
      (node (ref "J4") (pin "1") (pinfunction "1_1") (pintype "passive"))
    )
    (net (code "62") (name "/RC_SERVO_1") (class "Default")
      (node (ref "J6") (pin "1") (pinfunction "1_1") (pintype "passive"))
      (node (ref "U14") (pin "40") (pinfunction "OSC2/CLKO/RA6_40") (pintype "output"))
    )
    (net (code "63") (name "/RC_SERVO_2") (class "Default")
      (node (ref "J6") (pin "4") (pinfunction "4_4") (pintype "passive"))
      (node (ref "U14") (pin "39") (pinfunction "OSC1/CLKI/RA7_39") (pintype "input"))
    )
    (net (code "64") (name "/RC_SERVO_3") (class "Default")
      (node (ref "J6") (pin "7") (pinfunction "7_7") (pintype "passive"))
      (node (ref "U14") (pin "30") (pinfunction "RC0/SOSCO/SCLKI_30") (pintype "bidirectional"))
    )
    (net (code "65") (name "/RC_SERVO_4") (class "Default")
      (node (ref "J6") (pin "10") (pinfunction "10_10") (pintype "passive"))
      (node (ref "U14") (pin "29") (pinfunction "RC1/SOSCI/ECCP2/P2A_29") (pintype "bidirectional"))
    )
    (net (code "66") (name "/RC_SERVO_5") (class "Default")
      (node (ref "J20") (pin "3") (pinfunction "3_3") (pintype "passive"))
      (node (ref "U14") (pin "33") (pinfunction "RC2/ECCP1/P1A_33") (pintype "bidirectional"))
    )
    (net (code "67") (name "/RC_SERVO_6") (class "Default")
      (node (ref "J20") (pin "6") (pinfunction "6_6") (pintype "passive"))
      (node (ref "U14") (pin "34") (pinfunction "RC3/SCK1/SCL1_34") (pintype "bidirectional"))
    )
    (net (code "68") (name "/RC_SERVO_7") (class "Default")
      (node (ref "J20") (pin "9") (pinfunction "9_9") (pintype "passive"))
      (node (ref "U14") (pin "35") (pinfunction "RC4/SDI1/SDA1_35") (pintype "bidirectional"))
    )
    (net (code "69") (name "/RC_SERVO_8") (class "Default")
      (node (ref "J20") (pin "12") (pinfunction "12_12") (pintype "passive"))
      (node (ref "U14") (pin "36") (pinfunction "RC5/SDO1_36") (pintype "bidirectional"))
    )
    (net (code "70") (name "/RX0") (class "Default")
      (node (ref "J14") (pin "4") (pinfunction "4_4") (pintype "passive"))
      (node (ref "J3") (pin "4") (pinfunction "4_4") (pintype "passive"))
    )
    (net (code "71") (name "/RX1") (class "Default")
      (node (ref "J12") (pin "4") (pinfunction "4_4") (pintype "passive"))
      (node (ref "J3") (pin "6") (pinfunction "6_6") (pintype "passive"))
    )
    (net (code "72") (name "/SCL") (class "Default")
      (node (ref "J20") (pin "47") (pinfunction "47_47") (pintype "passive"))
      (node (ref "J20") (pin "50") (pinfunction "50_50") (pintype "passive"))
      (node (ref "J6") (pin "47") (pinfunction "47_47") (pintype "passive"))
      (node (ref "J6") (pin "50") (pinfunction "50_50") (pintype "passive"))
      (node (ref "R33") (pin "1") (pinfunction "1_1") (pintype "passive"))
      (node (ref "U14") (pin "50") (pinfunction "RD6/PSP6/SCK2/SCL2_50") (pintype "bidirectional"))
      (node (ref "U9") (pin "6") (pinfunction "SCL2_6") (pintype "bidirectional"))
    )
    (net (code "73") (name "/SCL_BFIN") (class "Default")
      (node (ref "J3") (pin "14") (pinfunction "14_14") (pintype "passive"))
      (node (ref "U9") (pin "3") (pinfunction "SCL1_3") (pintype "bidirectional"))
    )
    (net (code "74") (name "/SDA") (class "Default")
      (node (ref "J20") (pin "48") (pinfunction "48_48") (pintype "passive"))
      (node (ref "J20") (pin "51") (pinfunction "51_51") (pintype "passive"))
      (node (ref "J6") (pin "46") (pinfunction "46_46") (pintype "passive"))
      (node (ref "J6") (pin "49") (pinfunction "49_49") (pintype "passive"))
      (node (ref "R34") (pin "1") (pinfunction "1_1") (pintype "passive"))
      (node (ref "U14") (pin "51") (pinfunction "RD5/PSP5/SDI2/SDA2_51") (pintype "bidirectional"))
      (node (ref "U9") (pin "5") (pinfunction "SDA2_5") (pintype "bidirectional"))
    )
    (net (code "75") (name "/SDA_BFIN") (class "Default")
      (node (ref "J3") (pin "15") (pinfunction "15_15") (pintype "passive"))
      (node (ref "U9") (pin "4") (pinfunction "SDA1_4") (pintype "bidirectional"))
    )
    (net (code "76") (name "/SPI_SEL") (class "Default")
      (node (ref "J11") (pin "4") (pinfunction "4_4") (pintype "passive"))
      (node (ref "J16") (pin "4") (pinfunction "4_4") (pintype "passive"))
      (node (ref "J3") (pin "12") (pinfunction "12_12") (pintype "passive"))
    )
    (net (code "77") (name "/SPI_SEL2") (class "Default")
      (node (ref "J3") (pin "13") (pinfunction "13_13") (pintype "passive"))
      (node (ref "J4") (pin "4") (pinfunction "4_4") (pintype "passive"))
    )
    (net (code "78") (name "/TMR2") (class "Default")
      (node (ref "J16") (pin "1") (pinfunction "1_1") (pintype "passive"))
      (node (ref "J3") (pin "7") (pinfunction "7_7") (pintype "passive"))
    )
    (net (code "79") (name "/TMR3") (class "Default")
      (node (ref "J16") (pin "2") (pinfunction "2_2") (pintype "passive"))
      (node (ref "J3") (pin "8") (pinfunction "8_8") (pintype "passive"))
    )
    (net (code "80") (name "/TX0") (class "Default")
      (node (ref "J14") (pin "3") (pinfunction "3_3") (pintype "passive"))
      (node (ref "J3") (pin "3") (pinfunction "3_3") (pintype "passive"))
    )
    (net (code "81") (name "/TX1") (class "Default")
      (node (ref "J12") (pin "3") (pinfunction "3_3") (pintype "passive"))
      (node (ref "J3") (pin "5") (pinfunction "5_5") (pintype "passive"))
    )
    (net (code "82") (name "/~{RST}") (class "Default")
      (node (ref "J7") (pin "1") (pinfunction "1_1") (pintype "passive"))
      (node (ref "R2") (pin "1") (pinfunction "1_1") (pintype "passive"))
      (node (ref "R3") (pin "2") (pinfunction "2_2") (pintype "passive"))
      (node (ref "R4") (pin "1") (pinfunction "1_1") (pintype "passive"))
    )
    (net (code "83") (name "3.3V") (class "Default")
      (node (ref "C1") (pin "A") (pinfunction "+_A") (pintype "passive"))
      (node (ref "J15") (pin "1") (pinfunction "1_1") (pintype "passive"))
      (node (ref "J15") (pin "3") (pinfunction "3_3") (pintype "passive"))
      (node (ref "J3") (pin "1") (pinfunction "1_1") (pintype "passive"))
      (node (ref "U1") (pin "3") (pinfunction "OUT_3") (pintype "bidirectional"))
      (node (ref "U9") (pin "2") (pinfunction "VR1_2") (pintype "bidirectional"))
    )
    (net (code "84") (name "GND") (class "Default")
      (node (ref "C1") (pin "C") (pinfunction "-_C") (pintype "passive"))
      (node (ref "C10") (pin "1") (pinfunction "1_1") (pintype "passive"))
      (node (ref "C11") (pin "1") (pinfunction "1_1") (pintype "passive"))
      (node (ref "C12") (pin "2") (pinfunction "2_2") (pintype "passive"))
      (node (ref "C13") (pin "2") (pinfunction "2_2") (pintype "passive"))
      (node (ref "C14") (pin "2") (pinfunction "2_2") (pintype "passive"))
      (node (ref "C15") (pin "-") (pinfunction "-_-") (pintype "passive"))
      (node (ref "C16") (pin "2") (pinfunction "2_2") (pintype "passive"))
      (node (ref "C17") (pin "-") (pinfunction "-_-") (pintype "passive"))
      (node (ref "C18") (pin "2") (pinfunction "2_2") (pintype "passive"))
      (node (ref "C19") (pin "1") (pinfunction "1_1") (pintype "passive"))
      (node (ref "C2") (pin "2") (pinfunction "-_2") (pintype "passive"))
      (node (ref "C23") (pin "2") (pinfunction "2_2") (pintype "passive"))
      (node (ref "C24") (pin "2") (pinfunction "-_2") (pintype "passive"))
      (node (ref "C25") (pin "2") (pinfunction "2_2") (pintype "passive"))
      (node (ref "C27") (pin "1") (pinfunction "1_1") (pintype "passive"))
      (node (ref "C3") (pin "1") (pinfunction "1_1") (pintype "passive"))
      (node (ref "C4") (pin "-") (pinfunction "-_-") (pintype "passive"))
      (node (ref "C5") (pin "-") (pinfunction "-_-") (pintype "passive"))
      (node (ref "C6") (pin "-") (pinfunction "-_-") (pintype "passive"))
      (node (ref "C7") (pin "2") (pinfunction "2_2") (pintype "passive"))
      (node (ref "C8") (pin "-") (pinfunction "-_-") (pintype "passive"))
      (node (ref "C9") (pin "2") (pinfunction "2_2") (pintype "passive"))
      (node (ref "D1") (pin "A") (pinfunction "A_A") (pintype "passive"))
      (node (ref "J11") (pin "5") (pinfunction "5_5") (pintype "passive"))
      (node (ref "J12") (pin "2") (pinfunction "2_2") (pintype "passive"))
      (node (ref "J13") (pin "3") (pinfunction "3_3") (pintype "passive"))
      (node (ref "J14") (pin "2") (pinfunction "2_2") (pintype "passive"))
      (node (ref "J15") (pin "2") (pinfunction "2_2") (pintype "passive"))
      (node (ref "J15") (pin "4") (pinfunction "4_4") (pintype "passive"))
      (node (ref "J16") (pin "3") (pinfunction "3_3") (pintype "passive"))
      (node (ref "J20") (pin "1") (pinfunction "1_1") (pintype "passive"))
      (node (ref "J20") (pin "10") (pinfunction "10_10") (pintype "passive"))
      (node (ref "J20") (pin "13") (pinfunction "13_13") (pintype "passive"))
      (node (ref "J20") (pin "16") (pinfunction "16_16") (pintype "passive"))
      (node (ref "J20") (pin "19") (pinfunction "19_19") (pintype "passive"))
      (node (ref "J20") (pin "22") (pinfunction "22_22") (pintype "passive"))
      (node (ref "J20") (pin "25") (pinfunction "25_25") (pintype "passive"))
      (node (ref "J20") (pin "28") (pinfunction "28_28") (pintype "passive"))
      (node (ref "J20") (pin "31") (pinfunction "31_31") (pintype "passive"))
      (node (ref "J20") (pin "34") (pinfunction "34_34") (pintype "passive"))
      (node (ref "J20") (pin "37") (pinfunction "37_37") (pintype "passive"))
      (node (ref "J20") (pin "4") (pinfunction "4_4") (pintype "passive"))
      (node (ref "J20") (pin "40") (pinfunction "40_40") (pintype "passive"))
      (node (ref "J20") (pin "43") (pinfunction "43_43") (pintype "passive"))
      (node (ref "J20") (pin "46") (pinfunction "46_46") (pintype "passive"))
      (node (ref "J20") (pin "49") (pinfunction "49_49") (pintype "passive"))
      (node (ref "J20") (pin "7") (pinfunction "7_7") (pintype "passive"))
      (node (ref "J3") (pin "16") (pinfunction "16_16") (pintype "passive"))
      (node (ref "J3") (pin "2") (pinfunction "2_2") (pintype "passive"))
      (node (ref "J4") (pin "5") (pinfunction "5_5") (pintype "passive"))
      (node (ref "J5") (pin "2") (pinfunction "2_2") (pintype "passive"))
      (node (ref "J6") (pin "12") (pinfunction "12_12") (pintype "passive"))
      (node (ref "J6") (pin "15") (pinfunction "15_15") (pintype "passive"))
      (node (ref "J6") (pin "18") (pinfunction "18_18") (pintype "passive"))
      (node (ref "J6") (pin "21") (pinfunction "21_21") (pintype "passive"))
      (node (ref "J6") (pin "24") (pinfunction "24_24") (pintype "passive"))
      (node (ref "J6") (pin "27") (pinfunction "27_27") (pintype "passive"))
      (node (ref "J6") (pin "3") (pinfunction "3_3") (pintype "passive"))
      (node (ref "J6") (pin "30") (pinfunction "30_30") (pintype "passive"))
      (node (ref "J6") (pin "33") (pinfunction "33_33") (pintype "passive"))
      (node (ref "J6") (pin "36") (pinfunction "36_36") (pintype "passive"))
      (node (ref "J6") (pin "39") (pinfunction "39_39") (pintype "passive"))
      (node (ref "J6") (pin "42") (pinfunction "42_42") (pintype "passive"))
      (node (ref "J6") (pin "45") (pinfunction "45_45") (pintype "passive"))
      (node (ref "J6") (pin "48") (pinfunction "48_48") (pintype "passive"))
      (node (ref "J6") (pin "51") (pinfunction "51_51") (pintype "passive"))
      (node (ref "J6") (pin "6") (pinfunction "6_6") (pintype "passive"))
      (node (ref "J6") (pin "9") (pinfunction "9_9") (pintype "passive"))
      (node (ref "J7") (pin "3") (pinfunction "3_3") (pintype "passive"))
      (node (ref "J8") (pin "10") (pinfunction "10_10") (pintype "passive"))
      (node (ref "R23") (pin "1") (pinfunction "1_1") (pintype "passive"))
      (node (ref "U1") (pin "2") (pinfunction "GND_2") (pintype "bidirectional"))
      (node (ref "U11") (pin "1") (pinfunction "GND_1") (pintype "bidirectional"))
      (node (ref "U14") (pin "20") (pinfunction "AVSS_20") (pintype "power_in"))
      (node (ref "U14") (pin "25") (pinfunction "VSS_25") (pintype "power_in"))
      (node (ref "U14") (pin "41") (pinfunction "VSS_41") (pintype "power_in"))
      (node (ref "U14") (pin "56") (pinfunction "VSS_56") (pintype "power_in"))
      (node (ref "U14") (pin "9") (pinfunction "VSS_9") (pintype "power_in"))
      (node (ref "U15") (pin "10") (pinfunction "GND_10") (pintype "power_in"))
      (node (ref "U15") (pin "2") (pinfunction "RTRY_2") (pintype "input"))
      (node (ref "U15") (pin "8") (pinfunction "LSS_8") (pintype "output"))
      (node (ref "U15") (pin "PAD") (pinfunction "PAD_PAD") (pintype "output"))
      (node (ref "U2") (pin "3") (pinfunction "GND_3") (pintype "bidirectional"))
      (node (ref "U2") (pin "5") (pinfunction "SD_5") (pintype "bidirectional"))
      (node (ref "U2") (pin "6") (pinfunction "GND_6") (pintype "bidirectional"))
      (node (ref "U3") (pin "10") (pinfunction "GND_10") (pintype "power_in"))
      (node (ref "U3") (pin "2") (pinfunction "RTRY_2") (pintype "input"))
      (node (ref "U3") (pin "8") (pinfunction "LSS_8") (pintype "output"))
      (node (ref "U3") (pin "PAD") (pinfunction "PAD_PAD") (pintype "output"))
      (node (ref "U4") (pin "10") (pinfunction "GND_10") (pintype "power_in"))
      (node (ref "U4") (pin "2") (pinfunction "RTRY_2") (pintype "input"))
      (node (ref "U4") (pin "8") (pinfunction "LSS_8") (pintype "output"))
      (node (ref "U4") (pin "PAD") (pinfunction "PAD_PAD") (pintype "output"))
      (node (ref "U5") (pin "10") (pinfunction "GND_10") (pintype "power_in"))
      (node (ref "U5") (pin "2") (pinfunction "RTRY_2") (pintype "input"))
      (node (ref "U5") (pin "8") (pinfunction "LSS_8") (pintype "output"))
      (node (ref "U5") (pin "PAD") (pinfunction "PAD_PAD") (pintype "output"))
      (node (ref "U9") (pin "1") (pinfunction "GND_1") (pintype "bidirectional"))
    )
    (net (code "85") (name "Net-(C19-Pad2)") (class "Default")
      (node (ref "C19") (pin "2") (pinfunction "2_2") (pintype "passive"))
      (node (ref "R4") (pin "2") (pinfunction "2_2") (pintype "passive"))
    )
    (net (code "86") (name "Net-(D2-A)") (class "Default")
      (node (ref "D2") (pin "2") (pinfunction "A_2") (pintype "passive"))
      (node (ref "J5") (pin "1") (pinfunction "1_1") (pintype "passive"))
    )
    (net (code "87") (name "Net-(D4-A)") (class "Default")
      (node (ref "D4") (pin "2") (pinfunction "A_2") (pintype "passive"))
      (node (ref "J20") (pin "14") (pinfunction "14_14") (pintype "passive"))
    )
    (net (code "88") (name "Net-(D4-C)") (class "Default")
      (node (ref "D4") (pin "1") (pinfunction "C_1") (pintype "passive"))
      (node (ref "J20") (pin "11") (pinfunction "11_11") (pintype "passive"))
      (node (ref "J20") (pin "2") (pinfunction "2_2") (pintype "passive"))
      (node (ref "J20") (pin "5") (pinfunction "5_5") (pintype "passive"))
      (node (ref "J20") (pin "8") (pinfunction "8_8") (pintype "passive"))
    )
    (net (code "89") (name "Net-(D6-A)") (class "Default")
      (node (ref "D6") (pin "2") (pinfunction "A_2") (pintype "passive"))
      (node (ref "J6") (pin "14") (pinfunction "14_14") (pintype "passive"))
    )
    (net (code "90") (name "Net-(D6-C)") (class "Default")
      (node (ref "D6") (pin "1") (pinfunction "C_1") (pintype "passive"))
      (node (ref "J6") (pin "11") (pinfunction "11_11") (pintype "passive"))
      (node (ref "J6") (pin "2") (pinfunction "2_2") (pintype "passive"))
      (node (ref "J6") (pin "5") (pinfunction "5_5") (pintype "passive"))
      (node (ref "J6") (pin "8") (pinfunction "8_8") (pintype "passive"))
    )
    (net (code "91") (name "Net-(LED1-PadC)") (class "Default")
      (node (ref "LED1") (pin "C") (pinfunction "C_C") (pintype "passive"))
      (node (ref "R19") (pin "1") (pinfunction "1_1") (pintype "passive"))
    )
    (net (code "92") (name "Net-(U2-FB)") (class "Default")
      (node (ref "R22") (pin "1") (pinfunction "1_1") (pintype "passive"))
      (node (ref "R23") (pin "2") (pinfunction "2_2") (pintype "passive"))
      (node (ref "U2") (pin "4") (pinfunction "FB_4") (pintype "bidirectional"))
    )
    (net (code "93") (name "Net-(U2-OUT)") (class "Default")
      (node (ref "D1") (pin "C") (pinfunction "C_C") (pintype "passive"))
      (node (ref "L1") (pin "1") (pinfunction "1_1") (pintype "passive"))
      (node (ref "U2") (pin "2") (pinfunction "OUT_2") (pintype "bidirectional"))
    )
    (net (code "94") (name "Net-(U3-OUT1)") (class "Default")
      (node (ref "J2") (pin "3") (pinfunction "3_3") (pintype "passive"))
      (node (ref "U3") (pin "7") (pinfunction "OUT1_7") (pintype "output"))
    )
    (net (code "95") (name "Net-(U3-OUT2)") (class "Default")
      (node (ref "J2") (pin "4") (pinfunction "4_4") (pintype "passive"))
      (node (ref "U3") (pin "9") (pinfunction "OUT2_9") (pintype "input"))
    )
    (net (code "96") (name "Net-(U4-OUT1)") (class "Default")
      (node (ref "J1") (pin "2") (pinfunction "2_2") (pintype "passive"))
      (node (ref "U4") (pin "7") (pinfunction "OUT1_7") (pintype "output"))
    )
    (net (code "97") (name "Net-(U4-OUT2)") (class "Default")
      (node (ref "J1") (pin "1") (pinfunction "1_1") (pintype "passive"))
      (node (ref "U4") (pin "9") (pinfunction "OUT2_9") (pintype "input"))
    )
    (net (code "98") (name "Net-(U5-OUT1)") (class "Default")
      (node (ref "J1") (pin "4") (pinfunction "4_4") (pintype "passive"))
      (node (ref "U5") (pin "7") (pinfunction "OUT1_7") (pintype "output"))
    )
    (net (code "99") (name "Net-(U5-OUT2)") (class "Default")
      (node (ref "J1") (pin "3") (pinfunction "3_3") (pintype "passive"))
      (node (ref "U5") (pin "9") (pinfunction "OUT2_9") (pintype "input"))
    )
    (net (code "100") (name "Net-(U9-EN)") (class "Default")
      (node (ref "C27") (pin "2") (pinfunction "2_2") (pintype "passive"))
      (node (ref "R32") (pin "1") (pinfunction "1_1") (pintype "passive"))
      (node (ref "U9") (pin "7") (pinfunction "VR2_7") (pintype "bidirectional"))
      (node (ref "U9") (pin "8") (pinfunction "EN_8") (pintype "input"))
    )
    (net (code "101") (name "Net-(U14-AVDD)") (class "Default")
      (node (ref "C9") (pin "1") (pinfunction "1_1") (pintype "passive"))
      (node (ref "R1") (pin "2") (pinfunction "2_2") (pintype "passive"))
      (node (ref "U14") (pin "19") (pinfunction "AVDD_19") (pintype "power_in"))
    )
    (net (code "102") (name "Net-(U14-VDDCORE{slash}VCAP)") (class "Default")
      (node (ref "C3") (pin "2") (pinfunction "2_2") (pintype "passive"))
      (node (ref "U14") (pin "10") (pinfunction "VDDCORE/VCAP_10") (pintype "power_in"))
    )
    (net (code "103") (name "Net-(U14-~{MCLR{slash}}RG5)") (class "Default")
      (node (ref "R3") (pin "1") (pinfunction "1_1") (pintype "passive"))
      (node (ref "U14") (pin "7") (pinfunction "~{MCLR/}RG5_7") (pintype "input"))
    )
    (net (code "104") (name "Net-(U15-OUT1)") (class "Default")
      (node (ref "J2") (pin "1") (pinfunction "1_1") (pintype "passive"))
      (node (ref "U15") (pin "7") (pinfunction "OUT1_7") (pintype "output"))
    )
    (net (code "105") (name "Net-(U15-OUT2)") (class "Default")
      (node (ref "J2") (pin "2") (pinfunction "2_2") (pintype "passive"))
      (node (ref "U15") (pin "9") (pinfunction "OUT2_9") (pintype "input"))
    )
    (net (code "106") (name "unconnected-(J12-Pad1)") (class "Default")
      (node (ref "J12") (pin "1") (pinfunction "1_1") (pintype "passive"))
    )
    (net (code "107") (name "unconnected-(J14-Pad1)") (class "Default")
      (node (ref "J14") (pin "1") (pinfunction "1_1") (pintype "passive"))
    )
    (net (code "108") (name "unconnected-(U$1-1-PadP$2)") (class "Default")
      (node (ref "U$1") (pin "P$2") (pinfunction "1_P$2") (pintype "bidirectional"))
    )
    (net (code "109") (name "unconnected-(U$2-1-PadP$2)") (class "Default")
      (node (ref "U$2") (pin "P$2") (pinfunction "1_P$2") (pintype "bidirectional"))
    )
    (net (code "110") (name "unconnected-(U$7-1-PadP$2)") (class "Default")
      (node (ref "U$7") (pin "P$2") (pinfunction "1_P$2") (pintype "bidirectional"))
    )
    (net (code "111") (name "unconnected-(U$8-1-PadP$2)") (class "Default")
      (node (ref "U$8") (pin "P$2") (pinfunction "1_P$2") (pintype "bidirectional"))
    )
    (net (code "112") (name "unconnected-(U3-FAULT-Pad1)") (class "Default")
      (node (ref "U3") (pin "1") (pinfunction "FAULT_1") (pintype "output"))
    )
    (net (code "113") (name "unconnected-(U4-FAULT-Pad1)") (class "Default")
      (node (ref "U4") (pin "1") (pinfunction "FAULT_1") (pintype "output"))
    )
    (net (code "114") (name "unconnected-(U5-FAULT-Pad1)") (class "Default")
      (node (ref "U5") (pin "1") (pinfunction "FAULT_1") (pintype "output"))
    )
    (net (code "115") (name "unconnected-(U14-RE0{slash}~{RD{slash}}P2D-Pad2)") (class "Default")
      (node (ref "U14") (pin "2") (pinfunction "RE0/~{RD/}P2D_2") (pintype "bidirectional"))
    )
    (net (code "116") (name "unconnected-(U14-RE1{slash}~{WR{slash}}P2C-Pad1)") (class "Default")
      (node (ref "U14") (pin "1") (pinfunction "RE1/~{WR/}P2C_1") (pintype "bidirectional"))
    )
    (net (code "117") (name "unconnected-(U14-RG0{slash}ECCP3{slash}P3A-Pad3)") (class "Default")
      (node (ref "U14") (pin "3") (pinfunction "RG0/ECCP3/P3A_3") (pintype "bidirectional"))
    )
    (net (code "118") (name "unconnected-(U15-FAULT-Pad1)") (class "Default")
      (node (ref "U15") (pin "1") (pinfunction "FAULT_1") (pintype "output"))
    )
  )
)
